# POWER_SUPPLY_2.net
KiCad netlist of a schematic drawn in Altium Designer
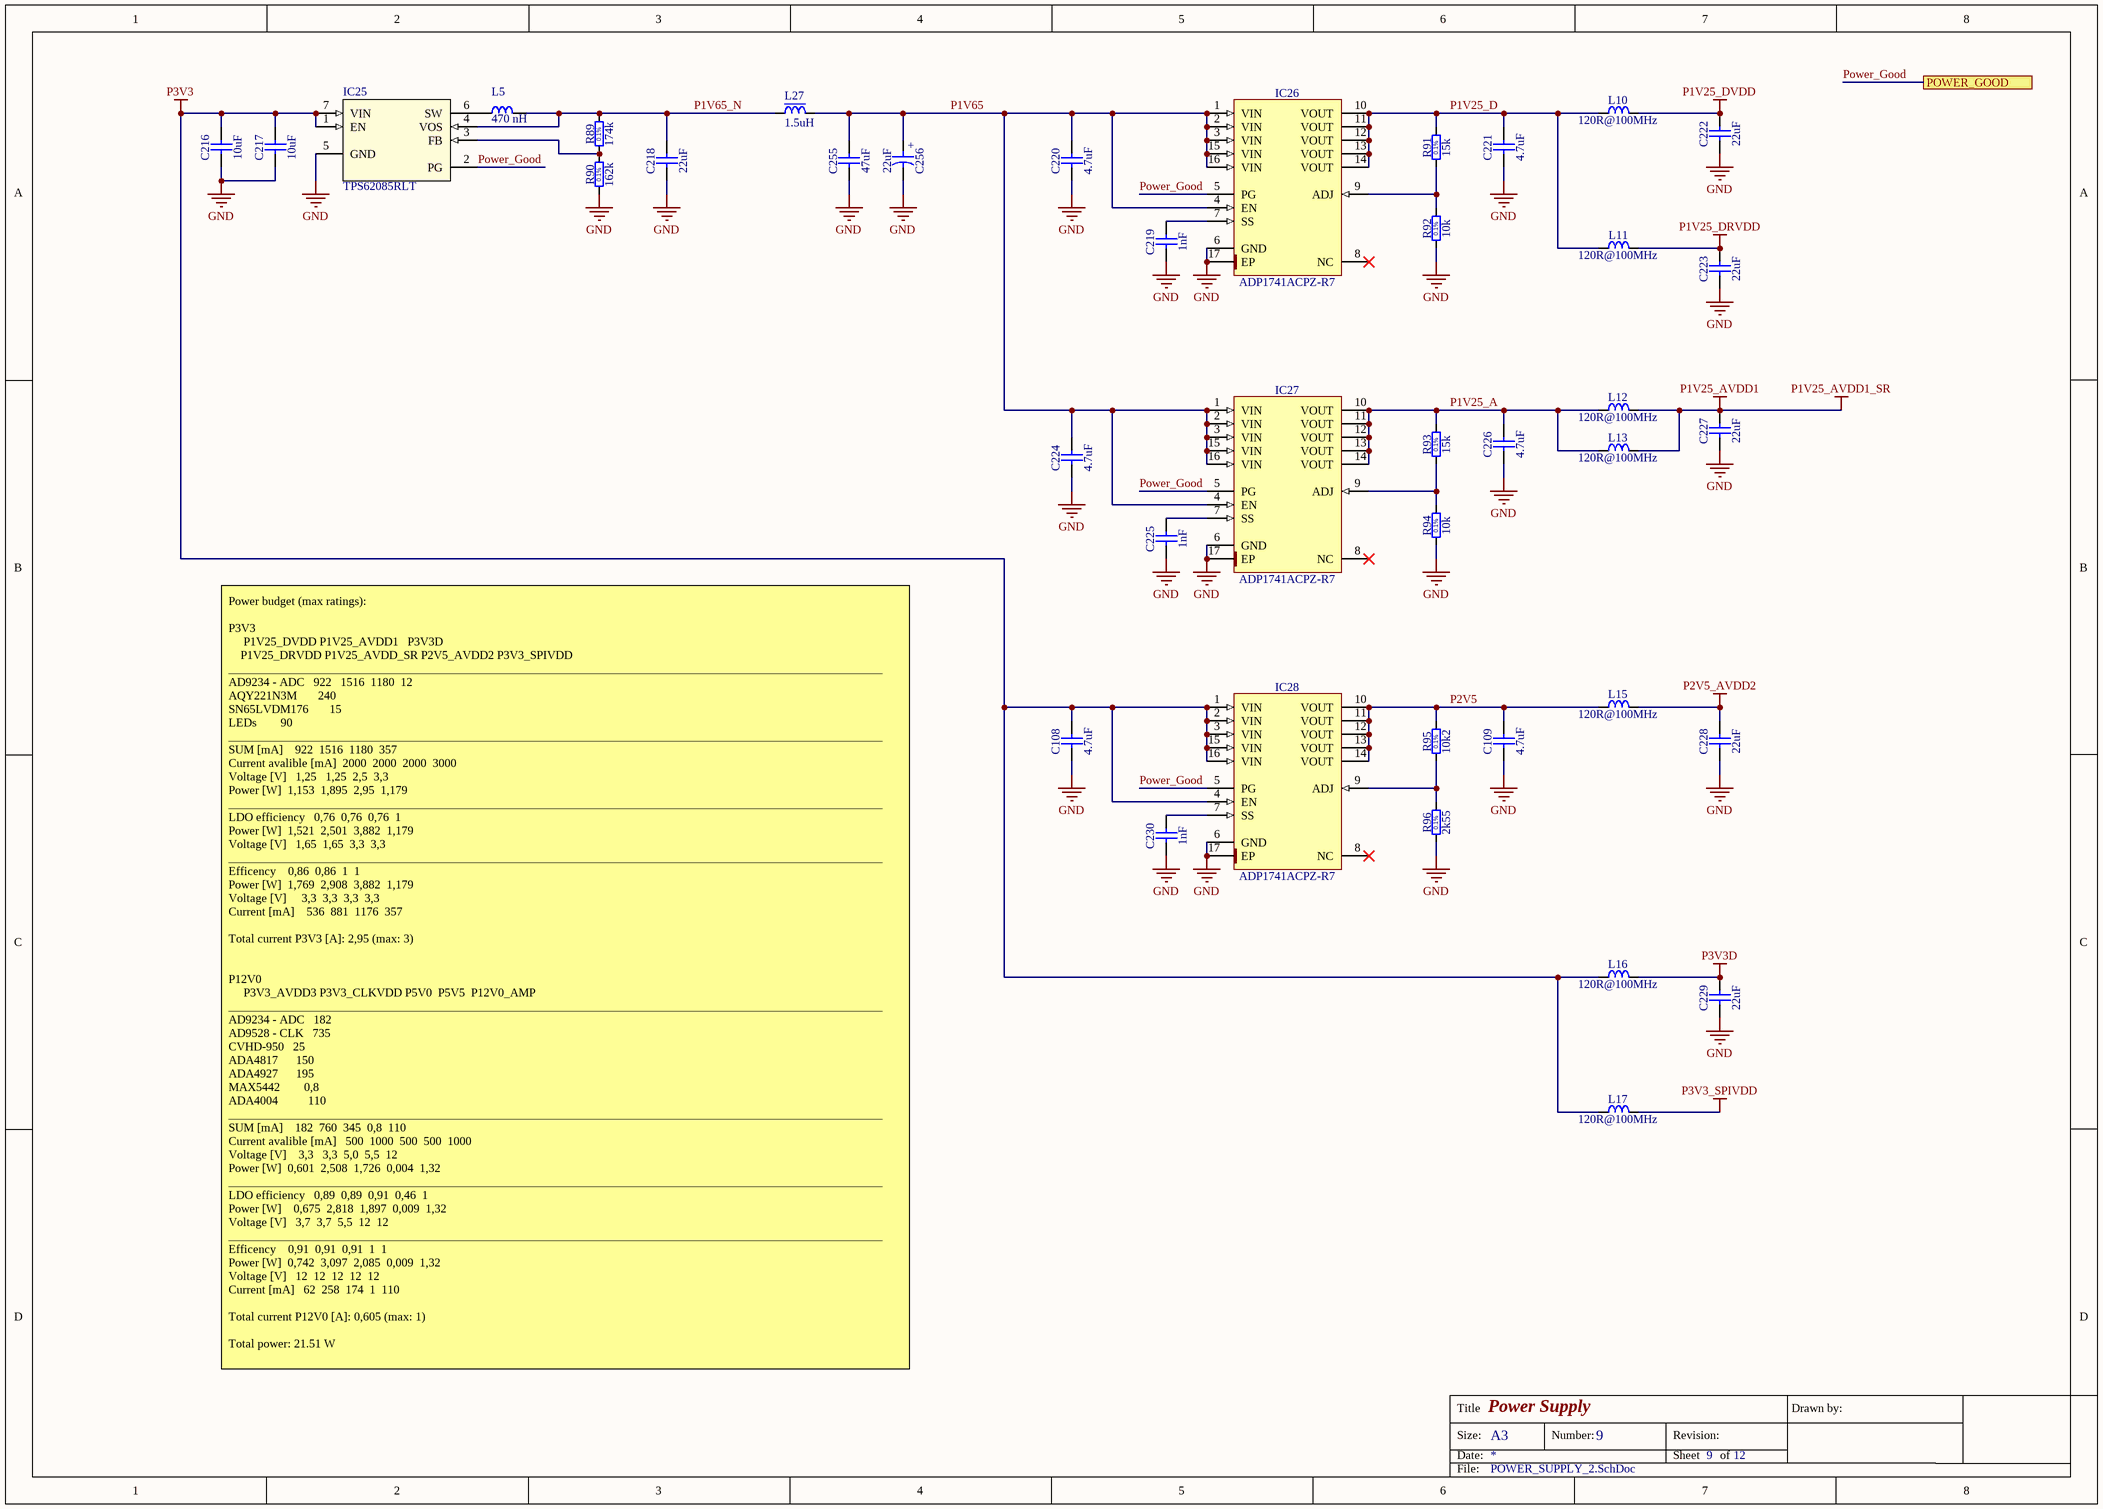
[diagram p0: POWER_SUPPLY_2.SchDoc]

(export (version "E")
  (design (tool "Eeschema 10.0.6"))
  (components
    (comp (ref "C108")
      (value "4.7uF")
      (footprint "CAPC1709X95N")
      (description "Non-polarised capacitor")
      (fields
        (field (name "PART NUMBER") "CC0603_4.7UF_16V_10%_X5R")
        (field (name "VOLTAGE") "16V")
        (field (name "AUTHOR") "CERN DEM JLC")
      )
      (libsource (lib "Capacitors") (part "Capacitor - non polarized"))
    )
    (comp (ref "C109")
      (value "4.7uF")
      (footprint "CAPC1709X95N")
      (description "Non-polarised capacitor")
      (fields
        (field (name "PART NUMBER") "CC0603_4.7UF_16V_10%_X5R")
        (field (name "VOLTAGE") "16V")
        (field (name "AUTHOR") "CERN DEM JLC")
      )
      (libsource (lib "Capacitors") (part "Capacitor - non polarized"))
    )
    (comp (ref "C216")
      (value "10uF")
      (footprint "CAPC1608X87N")
      (description "Non-polarised capacitor")
      (fields
        (field (name "PART NUMBER") "CC0603_10UF_6.3V_20%_X5R")
        (field (name "VOLTAGE") "6.3V")
        (field (name "AUTHOR") "CERN DEM JLC")
      )
      (libsource (lib "Capacitors") (part "Capacitor - non polarized"))
    )
    (comp (ref "C217")
      (value "10uF")
      (footprint "CAPC1608X87N")
      (description "Non-polarised capacitor")
      (fields
        (field (name "PART NUMBER") "CC0603_10UF_6.3V_20%_X5R")
        (field (name "VOLTAGE") "6.3V")
        (field (name "AUTHOR") "CERN DEM JLC")
      )
      (libsource (lib "Capacitors") (part "Capacitor - non polarized"))
    )
    (comp (ref "C218")
      (value "22uF")
      (footprint "CAPC2012X95N")
      (description "Non-polarised capacitor, Low ESR")
      (fields
        (field (name "PART NUMBER") "CC0805_22UF_6.3V_20%_X5R")
        (field (name "VOLTAGE") "6.3V")
        (field (name "AUTHOR") "*")
      )
      (libsource (lib "FMC_ADC") (part "JMK212ABJ226MD"))
    )
    (comp (ref "C219")
      (value "1nF")
      (footprint "CAPC0603X33N")
      (description "Non-polarised capacitor")
      (fields
        (field (name "PART NUMBER") "CC0201_1NF_16V_10%_X5R")
        (field (name "VOLTAGE") "16V")
        (field (name "AUTHOR") "CERN DEM JLC")
      )
      (libsource (lib "Capacitors") (part "Capacitor - non polarized"))
    )
    (comp (ref "C220")
      (value "4.7uF")
      (footprint "CAPC1709X95N")
      (description "Non-polarised capacitor")
      (fields
        (field (name "PART NUMBER") "CC0603_4.7UF_16V_10%_X5R")
        (field (name "VOLTAGE") "16V")
        (field (name "AUTHOR") "CERN DEM JLC")
      )
      (libsource (lib "Capacitors") (part "Capacitor - non polarized"))
    )
    (comp (ref "C221")
      (value "4.7uF")
      (footprint "CAPC1709X95N")
      (description "Non-polarised capacitor")
      (fields
        (field (name "PART NUMBER") "CC0603_4.7UF_16V_10%_X5R")
        (field (name "VOLTAGE") "16V")
        (field (name "AUTHOR") "CERN DEM JLC")
      )
      (libsource (lib "Capacitors") (part "Capacitor - non polarized"))
    )
    (comp (ref "C222")
      (value "22uF")
      (footprint "CAPC1709X100N")
      (description "Non-polarised capacitor")
      (fields
        (field (name "PART NUMBER") "CC0603_22UF_6.3V_20%_X5R")
        (field (name "VOLTAGE") "6.3V")
        (field (name "AUTHOR") "CERN DEM JLC")
      )
      (libsource (lib "Capacitors") (part "Capacitor - non polarized"))
    )
    (comp (ref "C223")
      (value "22uF")
      (footprint "CAPC1709X100N")
      (description "Non-polarised capacitor")
      (fields
        (field (name "PART NUMBER") "CC0603_22UF_6.3V_20%_X5R")
        (field (name "VOLTAGE") "6.3V")
        (field (name "AUTHOR") "CERN DEM JLC")
      )
      (libsource (lib "Capacitors") (part "Capacitor - non polarized"))
    )
    (comp (ref "C224")
      (value "4.7uF")
      (footprint "CAPC1709X95N")
      (description "Non-polarised capacitor")
      (fields
        (field (name "PART NUMBER") "CC0603_4.7UF_16V_10%_X5R")
        (field (name "VOLTAGE") "16V")
        (field (name "AUTHOR") "CERN DEM JLC")
      )
      (libsource (lib "Capacitors") (part "Capacitor - non polarized"))
    )
    (comp (ref "C225")
      (value "1nF")
      (footprint "CAPC0603X33N")
      (description "Non-polarised capacitor")
      (fields
        (field (name "PART NUMBER") "CC0201_1NF_16V_10%_X5R")
        (field (name "VOLTAGE") "16V")
        (field (name "AUTHOR") "CERN DEM JLC")
      )
      (libsource (lib "Capacitors") (part "Capacitor - non polarized"))
    )
    (comp (ref "C226")
      (value "4.7uF")
      (footprint "CAPC1709X95N")
      (description "Non-polarised capacitor")
      (fields
        (field (name "PART NUMBER") "CC0603_4.7UF_16V_10%_X5R")
        (field (name "VOLTAGE") "16V")
        (field (name "AUTHOR") "CERN DEM JLC")
      )
      (libsource (lib "Capacitors") (part "Capacitor - non polarized"))
    )
    (comp (ref "C227")
      (value "22uF")
      (footprint "CAPC1709X100N")
      (description "Non-polarised capacitor")
      (fields
        (field (name "PART NUMBER") "CC0603_22UF_6.3V_20%_X5R")
        (field (name "VOLTAGE") "6.3V")
        (field (name "AUTHOR") "CERN DEM JLC")
      )
      (libsource (lib "Capacitors") (part "Capacitor - non polarized"))
    )
    (comp (ref "C228")
      (value "22uF")
      (footprint "CAPC1709X100N")
      (description "Non-polarised capacitor")
      (fields
        (field (name "PART NUMBER") "CC0603_22UF_6.3V_20%_X5R")
        (field (name "VOLTAGE") "6.3V")
        (field (name "AUTHOR") "CERN DEM JLC")
      )
      (libsource (lib "Capacitors") (part "Capacitor - non polarized"))
    )
    (comp (ref "C229")
      (value "22uF")
      (footprint "CAPC1709X100N")
      (description "Non-polarised capacitor")
      (fields
        (field (name "PART NUMBER") "CC0603_22UF_6.3V_20%_X5R")
        (field (name "VOLTAGE") "6.3V")
        (field (name "AUTHOR") "CERN DEM JLC")
      )
      (libsource (lib "Capacitors") (part "Capacitor - non polarized"))
    )
    (comp (ref "C230")
      (value "1nF")
      (footprint "CAPC0603X33N")
      (description "Non-polarised capacitor")
      (fields
        (field (name "PART NUMBER") "CC0201_1NF_16V_10%_X5R")
        (field (name "VOLTAGE") "16V")
        (field (name "AUTHOR") "CERN DEM JLC")
      )
      (libsource (lib "Capacitors") (part "Capacitor - non polarized"))
    )
    (comp (ref "C255")
      (value "47uF")
      (footprint "CAPC3225X270N")
      (description "Non-polarised capacitor")
      (fields
        (field (name "PART NUMBER") "CC1210_47UF_10V_20%_X5R")
        (field (name "VOLTAGE") "10V")
        (field (name "AUTHOR") "CERN DEM JLC")
      )
      (libsource (lib "Capacitors") (part "Capacitor - non polarized"))
    )
    (comp (ref "C256")
      (value "22uF")
      (footprint "CAPMP3528X210N")
      (description "Polarised capacitor")
      (fields
        (field (name "PART NUMBER") "CTE3528-21_22UF_10V_10%_LESR0700")
        (field (name "VOLTAGE") "10V")
        (field (name "AUTHOR") "CERN DEM JLC")
      )
      (libsource (lib "Capacitors") (part "Capacitor - polarized"))
    )
    (comp (ref "IC25")
      (value "TPS62085RLT")
      (footprint "RLT0007A")
      (description "3-A Step-Down Converter With Hiccup Short-Circuit Protection")
      (fields (field (name "MANUFACTURER") "Texas Instruments"))
      (libsource (lib "FMC_ADC") (part "TPS62085RLT"))
    )
    (comp (ref "IC26")
      (value "ADP1741ACPZ-R7")
      (footprint "QFN65P400X400X100-17N-S225")
      (description "2A, 0.75V to 3.0V Adjustable, Low-Dropout Linear Regulator")
      (fields (field (name "MANUFACTURER") "ANALOG DEVICES") (field (name "AUTHOR") "CERN DEM JLC"))
      (libsource (lib "ICs And Semiconductors") (part "ADP1741"))
    )
    (comp (ref "IC27")
      (value "ADP1741ACPZ-R7")
      (footprint "QFN65P400X400X100-17N-S225")
      (description "2A, 0.75V to 3.0V Adjustable, Low-Dropout Linear Regulator")
      (fields (field (name "MANUFACTURER") "ANALOG DEVICES") (field (name "AUTHOR") "CERN DEM JLC"))
      (libsource (lib "ICs And Semiconductors") (part "ADP1741"))
    )
    (comp (ref "IC28")
      (value "ADP1741ACPZ-R7")
      (footprint "QFN65P400X400X100-17N-S225")
      (description "2A, 0.75V to 3.0V Adjustable, Low-Dropout Linear Regulator")
      (fields (field (name "MANUFACTURER") "ANALOG DEVICES") (field (name "AUTHOR") "CERN DEM JLC"))
      (libsource (lib "ICs And Semiconductors") (part "ADP1741"))
    )
    (comp (ref "L5")
      (value "470 nH")
      (footprint "IND_IHLP-1212AE")
      (description "Inductor, Low DCR Series")
      (fields (field (name "TOLERANCE") "20%") (field (name "MANUFACTURER") "VISHAY"))
      (libsource (lib "FMC_ADC") (part "IHLP1212AEERR47M11"))
    )
    (comp (ref "L10")
      (value "120R@100MHz")
      (footprint "INDC1608X65N")
      (description "Inductor")
      (fields
        (field (name "PART NUMBER") "IND0603_MURATA_BLM18SG121TN1D")
        (field (name "POWER") "3A")
        (field (name "AUTHOR") "CERN DEM JLC")
      )
      (libsource (lib "Inductors & Transformers") (part "Inductor"))
    )
    (comp (ref "L11")
      (value "120R@100MHz")
      (footprint "INDC1608X65N")
      (description "Inductor")
      (fields
        (field (name "PART NUMBER") "IND0603_MURATA_BLM18SG121TN1D")
        (field (name "POWER") "3A")
        (field (name "AUTHOR") "CERN DEM JLC")
      )
      (libsource (lib "Inductors & Transformers") (part "Inductor"))
    )
    (comp (ref "L12")
      (value "120R@100MHz")
      (footprint "INDC1608X65N")
      (description "Inductor")
      (fields
        (field (name "PART NUMBER") "IND0603_MURATA_BLM18SG121TN1D")
        (field (name "POWER") "3A")
        (field (name "AUTHOR") "CERN DEM JLC")
      )
      (libsource (lib "Inductors & Transformers") (part "Inductor"))
    )
    (comp (ref "L13")
      (value "120R@100MHz")
      (footprint "INDC1608X65N")
      (description "Inductor")
      (fields
        (field (name "PART NUMBER") "IND0603_MURATA_BLM18SG121TN1D")
        (field (name "POWER") "3A")
        (field (name "AUTHOR") "CERN DEM JLC")
      )
      (libsource (lib "Inductors & Transformers") (part "Inductor"))
    )
    (comp (ref "L15")
      (value "120R@100MHz")
      (footprint "INDC1608X65N")
      (description "Inductor")
      (fields
        (field (name "PART NUMBER") "IND0603_MURATA_BLM18SG121TN1D")
        (field (name "POWER") "3A")
        (field (name "AUTHOR") "CERN DEM JLC")
      )
      (libsource (lib "Inductors & Transformers") (part "Inductor"))
    )
    (comp (ref "L16")
      (value "120R@100MHz")
      (footprint "INDC1608X65N")
      (description "Inductor")
      (fields
        (field (name "PART NUMBER") "IND0603_MURATA_BLM18SG121TN1D")
        (field (name "POWER") "3A")
        (field (name "AUTHOR") "CERN DEM JLC")
      )
      (libsource (lib "Inductors & Transformers") (part "Inductor"))
    )
    (comp (ref "L17")
      (value "120R@100MHz")
      (footprint "INDC1608X65N")
      (description "Inductor")
      (fields
        (field (name "PART NUMBER") "IND0603_MURATA_BLM18SG121TN1D")
        (field (name "POWER") "3A")
        (field (name "AUTHOR") "CERN DEM JLC")
      )
      (libsource (lib "Inductors & Transformers") (part "Inductor"))
    )
    (comp (ref "L27")
      (value "1.5uH")
      (footprint "IND_SPM4020")
      (description "Inductor With Core")
      (fields
        (field (name "PART NUMBER") "IND_1.5UH_20%_TDK_SPM4020-LR")
        (field (name "POWER") "6.3A")
        (field (name "AUTHOR") "CERN DEM MR")
      )
      (libsource (lib "FMC_ADC") (part "IND_1.5UH_20%_TDK_SPM4020-LR"))
    )
    (comp (ref "R89")
      (value "174k")
      (footprint "RESC2012X60N")
      (description "Resistor - 0.1%")
      (fields
        (field (name "PART NUMBER") "R0805_174K_0.1%_0.125W_25PPM")
        (field (name "POWER") "0.125W")
        (field (name "AUTHOR") "CERN DEM JLC")
      )
      (libsource (lib "Resistors") (part "Resistor - 0.1%"))
    )
    (comp (ref "R90")
      (value "162k")
      (footprint "RESC2012X60N")
      (description "Resistor - 0.1%")
      (fields
        (field (name "PART NUMBER") "R0805_162K_0.1%_0.125W_25PPM")
        (field (name "POWER") "0.125W")
        (field (name "AUTHOR") "CERN DEM JLC")
      )
      (libsource (lib "Resistors") (part "Resistor - 0.1%"))
    )
    (comp (ref "R91")
      (value "15k")
      (footprint "RESC1608X55N")
      (description "Resistor - 0.1%")
      (fields
        (field (name "PART NUMBER") "R0603_15K_0.1%_0.063W_10PPM")
        (field (name "POWER") "0.063W")
        (field (name "AUTHOR") "CERN DEM JLC")
      )
      (libsource (lib "Resistors") (part "Resistor - 0.1%"))
    )
    (comp (ref "R92")
      (value "10k")
      (footprint "RESC1608X55N")
      (description "Resistor - 0.1%")
      (fields
        (field (name "PART NUMBER") "R0603_10K_0.1%_0.063W_10PPM")
        (field (name "POWER") "0.063W")
        (field (name "AUTHOR") "CERN DEM JLC")
      )
      (libsource (lib "Resistors") (part "Resistor - 0.1%"))
    )
    (comp (ref "R93")
      (value "15k")
      (footprint "RESC1608X55N")
      (description "Resistor - 0.1%")
      (fields
        (field (name "PART NUMBER") "R0603_15K_0.1%_0.063W_10PPM")
        (field (name "POWER") "0.063W")
        (field (name "AUTHOR") "CERN DEM JLC")
      )
      (libsource (lib "Resistors") (part "Resistor - 0.1%"))
    )
    (comp (ref "R94")
      (value "10k")
      (footprint "RESC1608X55N")
      (description "Resistor - 0.1%")
      (fields
        (field (name "PART NUMBER") "R0603_10K_0.1%_0.063W_10PPM")
        (field (name "POWER") "0.063W")
        (field (name "AUTHOR") "CERN DEM JLC")
      )
      (libsource (lib "Resistors") (part "Resistor - 0.1%"))
    )
    (comp (ref "R95")
      (value "10k2")
      (footprint "RESC1608X55N")
      (description "Resistor - 0.1%")
      (fields
        (field (name "PART NUMBER") "R0603_10K2_0.1%_0.063W_10PPM")
        (field (name "POWER") "0.063W")
        (field (name "AUTHOR") "CERN DEM JLC")
      )
      (libsource (lib "Resistors") (part "Resistor - 0.1%"))
    )
    (comp (ref "R96")
      (value "2k55")
      (footprint "RESC1608X55N")
      (description "Resistor - 0.1%")
      (fields
        (field (name "PART NUMBER") "R0603_2K55_0.1%_0.063W_10PPM")
        (field (name "POWER") "0.063W")
        (field (name "AUTHOR") "CERN DEM JLC")
      )
      (libsource (lib "Resistors") (part "Resistor - 0.1%"))
    )
  )
  (nets
    (net (code "1") (name "/P1V25_A") (class "Default")
      (node (ref "C226") (pin "2") (pinfunction "2_2") (pintype "passive"))
      (node (ref "IC27") (pin "10") (pinfunction "VOUT_10") (pintype "power_in"))
      (node (ref "IC27") (pin "11") (pinfunction "VOUT_11") (pintype "power_in"))
      (node (ref "IC27") (pin "12") (pinfunction "VOUT_12") (pintype "power_in"))
      (node (ref "IC27") (pin "13") (pinfunction "VOUT_13") (pintype "power_in"))
      (node (ref "IC27") (pin "14") (pinfunction "VOUT_14") (pintype "power_in"))
      (node (ref "L12") (pin "1") (pinfunction "1_1") (pintype "passive"))
      (node (ref "L13") (pin "1") (pinfunction "1_1") (pintype "passive"))
      (node (ref "R93") (pin "2") (pinfunction "2_2") (pintype "passive"))
    )
    (net (code "2") (name "/P1V25_D") (class "Default")
      (node (ref "C221") (pin "2") (pinfunction "2_2") (pintype "passive"))
      (node (ref "IC26") (pin "10") (pinfunction "VOUT_10") (pintype "power_in"))
      (node (ref "IC26") (pin "11") (pinfunction "VOUT_11") (pintype "power_in"))
      (node (ref "IC26") (pin "12") (pinfunction "VOUT_12") (pintype "power_in"))
      (node (ref "IC26") (pin "13") (pinfunction "VOUT_13") (pintype "power_in"))
      (node (ref "IC26") (pin "14") (pinfunction "VOUT_14") (pintype "power_in"))
      (node (ref "L10") (pin "1") (pinfunction "1_1") (pintype "passive"))
      (node (ref "L11") (pin "1") (pinfunction "1_1") (pintype "passive"))
      (node (ref "R91") (pin "2") (pinfunction "2_2") (pintype "passive"))
    )
    (net (code "3") (name "/P1V65") (class "Default")
      (node (ref "C220") (pin "2") (pinfunction "2_2") (pintype "passive"))
      (node (ref "C224") (pin "2") (pinfunction "2_2") (pintype "passive"))
      (node (ref "C255") (pin "2") (pinfunction "2_2") (pintype "passive"))
      (node (ref "C256") (pin "1") (pinfunction "1_1") (pintype "passive"))
      (node (ref "IC26") (pin "1") (pinfunction "VIN_1") (pintype "input"))
      (node (ref "IC26") (pin "15") (pinfunction "VIN_15") (pintype "input"))
      (node (ref "IC26") (pin "16") (pinfunction "VIN_16") (pintype "input"))
      (node (ref "IC26") (pin "2") (pinfunction "VIN_2") (pintype "input"))
      (node (ref "IC26") (pin "3") (pinfunction "VIN_3") (pintype "input"))
      (node (ref "IC26") (pin "4") (pinfunction "EN_4") (pintype "input"))
      (node (ref "IC27") (pin "1") (pinfunction "VIN_1") (pintype "input"))
      (node (ref "IC27") (pin "15") (pinfunction "VIN_15") (pintype "input"))
      (node (ref "IC27") (pin "16") (pinfunction "VIN_16") (pintype "input"))
      (node (ref "IC27") (pin "2") (pinfunction "VIN_2") (pintype "input"))
      (node (ref "IC27") (pin "3") (pinfunction "VIN_3") (pintype "input"))
      (node (ref "IC27") (pin "4") (pinfunction "EN_4") (pintype "input"))
      (node (ref "L27") (pin "2") (pinfunction "2_2") (pintype "passive"))
    )
    (net (code "4") (name "/P1V65_N") (class "Default")
      (node (ref "C218") (pin "2") (pinfunction "2_2") (pintype "passive"))
      (node (ref "IC25") (pin "4") (pinfunction "VOS_4") (pintype "input"))
      (node (ref "L27") (pin "1") (pinfunction "1_1") (pintype "passive"))
      (node (ref "L5") (pin "1") (pinfunction "1_1") (pintype "passive"))
      (node (ref "R89") (pin "2") (pinfunction "2_2") (pintype "passive"))
    )
    (net (code "5") (name "/P2V5") (class "Default")
      (node (ref "C109") (pin "2") (pinfunction "2_2") (pintype "passive"))
      (node (ref "IC28") (pin "10") (pinfunction "VOUT_10") (pintype "power_in"))
      (node (ref "IC28") (pin "11") (pinfunction "VOUT_11") (pintype "power_in"))
      (node (ref "IC28") (pin "12") (pinfunction "VOUT_12") (pintype "power_in"))
      (node (ref "IC28") (pin "13") (pinfunction "VOUT_13") (pintype "power_in"))
      (node (ref "IC28") (pin "14") (pinfunction "VOUT_14") (pintype "power_in"))
      (node (ref "L15") (pin "1") (pinfunction "1_1") (pintype "passive"))
      (node (ref "R95") (pin "2") (pinfunction "2_2") (pintype "passive"))
    )
    (net (code "6") (name "/Power_Good") (class "Default")
      (node (ref "IC25") (pin "2") (pinfunction "PG_2") (pintype "open_collector"))
      (node (ref "IC26") (pin "5") (pinfunction "PG_5") (pintype "open_collector"))
      (node (ref "IC27") (pin "5") (pinfunction "PG_5") (pintype "open_collector"))
      (node (ref "IC28") (pin "5") (pinfunction "PG_5") (pintype "open_collector"))
    )
    (net (code "7") (name "GND") (class "Default")
      (node (ref "C108") (pin "1") (pinfunction "1_1") (pintype "passive"))
      (node (ref "C109") (pin "1") (pinfunction "1_1") (pintype "passive"))
      (node (ref "C216") (pin "1") (pinfunction "1_1") (pintype "passive"))
      (node (ref "C217") (pin "1") (pinfunction "1_1") (pintype "passive"))
      (node (ref "C218") (pin "1") (pinfunction "1_1") (pintype "passive"))
      (node (ref "C219") (pin "1") (pinfunction "1_1") (pintype "passive"))
      (node (ref "C220") (pin "1") (pinfunction "1_1") (pintype "passive"))
      (node (ref "C221") (pin "1") (pinfunction "1_1") (pintype "passive"))
      (node (ref "C222") (pin "1") (pinfunction "1_1") (pintype "passive"))
      (node (ref "C223") (pin "1") (pinfunction "1_1") (pintype "passive"))
      (node (ref "C224") (pin "1") (pinfunction "1_1") (pintype "passive"))
      (node (ref "C225") (pin "1") (pinfunction "1_1") (pintype "passive"))
      (node (ref "C226") (pin "1") (pinfunction "1_1") (pintype "passive"))
      (node (ref "C227") (pin "1") (pinfunction "1_1") (pintype "passive"))
      (node (ref "C228") (pin "1") (pinfunction "1_1") (pintype "passive"))
      (node (ref "C229") (pin "1") (pinfunction "1_1") (pintype "passive"))
      (node (ref "C230") (pin "1") (pinfunction "1_1") (pintype "passive"))
      (node (ref "C255") (pin "1") (pinfunction "1_1") (pintype "passive"))
      (node (ref "C256") (pin "2") (pinfunction "2_2") (pintype "passive"))
      (node (ref "IC25") (pin "5") (pinfunction "GND_5") (pintype "power_in"))
      (node (ref "IC26") (pin "17") (pinfunction "EP_17") (pintype "power_in"))
      (node (ref "IC26") (pin "6") (pinfunction "GND_6") (pintype "power_in"))
      (node (ref "IC27") (pin "17") (pinfunction "EP_17") (pintype "power_in"))
      (node (ref "IC27") (pin "6") (pinfunction "GND_6") (pintype "power_in"))
      (node (ref "IC28") (pin "17") (pinfunction "EP_17") (pintype "power_in"))
      (node (ref "IC28") (pin "6") (pinfunction "GND_6") (pintype "power_in"))
      (node (ref "R90") (pin "1") (pinfunction "1_1") (pintype "passive"))
      (node (ref "R92") (pin "1") (pinfunction "1_1") (pintype "passive"))
      (node (ref "R94") (pin "1") (pinfunction "1_1") (pintype "passive"))
      (node (ref "R96") (pin "1") (pinfunction "1_1") (pintype "passive"))
    )
    (net (code "8") (name "Net-(IC25-FB)") (class "Default")
      (node (ref "IC25") (pin "3") (pinfunction "FB_3") (pintype "input"))
      (node (ref "R89") (pin "1") (pinfunction "1_1") (pintype "passive"))
      (node (ref "R90") (pin "2") (pinfunction "2_2") (pintype "passive"))
    )
    (net (code "9") (name "Net-(IC25-SW)") (class "Default")
      (node (ref "IC25") (pin "6") (pinfunction "SW_6") (pintype "power_in"))
      (node (ref "L5") (pin "2") (pinfunction "2_2") (pintype "passive"))
    )
    (net (code "10") (name "Net-(IC26-ADJ)") (class "Default")
      (node (ref "IC26") (pin "9") (pinfunction "ADJ_9") (pintype "input"))
      (node (ref "R91") (pin "1") (pinfunction "1_1") (pintype "passive"))
      (node (ref "R92") (pin "2") (pinfunction "2_2") (pintype "passive"))
    )
    (net (code "11") (name "Net-(IC26-SS)") (class "Default")
      (node (ref "C219") (pin "2") (pinfunction "2_2") (pintype "passive"))
      (node (ref "IC26") (pin "7") (pinfunction "SS_7") (pintype "input"))
    )
    (net (code "12") (name "Net-(IC27-ADJ)") (class "Default")
      (node (ref "IC27") (pin "9") (pinfunction "ADJ_9") (pintype "input"))
      (node (ref "R93") (pin "1") (pinfunction "1_1") (pintype "passive"))
      (node (ref "R94") (pin "2") (pinfunction "2_2") (pintype "passive"))
    )
    (net (code "13") (name "Net-(IC27-SS)") (class "Default")
      (node (ref "C225") (pin "2") (pinfunction "2_2") (pintype "passive"))
      (node (ref "IC27") (pin "7") (pinfunction "SS_7") (pintype "input"))
    )
    (net (code "14") (name "Net-(IC28-ADJ)") (class "Default")
      (node (ref "IC28") (pin "9") (pinfunction "ADJ_9") (pintype "input"))
      (node (ref "R95") (pin "1") (pinfunction "1_1") (pintype "passive"))
      (node (ref "R96") (pin "2") (pinfunction "2_2") (pintype "passive"))
    )
    (net (code "15") (name "Net-(IC28-SS)") (class "Default")
      (node (ref "C230") (pin "2") (pinfunction "2_2") (pintype "passive"))
      (node (ref "IC28") (pin "7") (pinfunction "SS_7") (pintype "input"))
    )
    (net (code "16") (name "P1V25_AVDD1") (class "Default")
      (node (ref "C227") (pin "2") (pinfunction "2_2") (pintype "passive"))
      (node (ref "L12") (pin "2") (pinfunction "2_2") (pintype "passive"))
      (node (ref "L13") (pin "2") (pinfunction "2_2") (pintype "passive"))
    )
    (net (code "17") (name "P1V25_DRVDD") (class "Default")
      (node (ref "C223") (pin "2") (pinfunction "2_2") (pintype "passive"))
      (node (ref "L11") (pin "2") (pinfunction "2_2") (pintype "passive"))
    )
    (net (code "18") (name "P1V25_DVDD") (class "Default")
      (node (ref "C222") (pin "2") (pinfunction "2_2") (pintype "passive"))
      (node (ref "L10") (pin "2") (pinfunction "2_2") (pintype "passive"))
    )
    (net (code "19") (name "P2V5_AVDD2") (class "Default")
      (node (ref "C228") (pin "2") (pinfunction "2_2") (pintype "passive"))
      (node (ref "L15") (pin "2") (pinfunction "2_2") (pintype "passive"))
    )
    (net (code "20") (name "P3V3") (class "Default")
      (node (ref "C108") (pin "2") (pinfunction "2_2") (pintype "passive"))
      (node (ref "C216") (pin "2") (pinfunction "2_2") (pintype "passive"))
      (node (ref "C217") (pin "2") (pinfunction "2_2") (pintype "passive"))
      (node (ref "IC25") (pin "1") (pinfunction "EN_1") (pintype "input"))
      (node (ref "IC25") (pin "7") (pinfunction "VIN_7") (pintype "input"))
      (node (ref "IC28") (pin "1") (pinfunction "VIN_1") (pintype "input"))
      (node (ref "IC28") (pin "15") (pinfunction "VIN_15") (pintype "input"))
      (node (ref "IC28") (pin "16") (pinfunction "VIN_16") (pintype "input"))
      (node (ref "IC28") (pin "2") (pinfunction "VIN_2") (pintype "input"))
      (node (ref "IC28") (pin "3") (pinfunction "VIN_3") (pintype "input"))
      (node (ref "IC28") (pin "4") (pinfunction "EN_4") (pintype "input"))
      (node (ref "L16") (pin "1") (pinfunction "1_1") (pintype "passive"))
      (node (ref "L17") (pin "1") (pinfunction "1_1") (pintype "passive"))
    )
    (net (code "21") (name "P3V3D") (class "Default")
      (node (ref "C229") (pin "2") (pinfunction "2_2") (pintype "passive"))
      (node (ref "L16") (pin "2") (pinfunction "2_2") (pintype "passive"))
    )
    (net (code "22") (name "P3V3_SPIVDD") (class "Default")
      (node (ref "L17") (pin "2") (pinfunction "2_2") (pintype "passive"))
    )
    (net (code "23") (name "unconnected-(IC26-NC-Pad8)") (class "Default")
      (node (ref "IC26") (pin "8") (pinfunction "NC_8") (pintype "passive+no_connect"))
    )
    (net (code "24") (name "unconnected-(IC27-NC-Pad8)") (class "Default")
      (node (ref "IC27") (pin "8") (pinfunction "NC_8") (pintype "passive+no_connect"))
    )
    (net (code "25") (name "unconnected-(IC28-NC-Pad8)") (class "Default")
      (node (ref "IC28") (pin "8") (pinfunction "NC_8") (pintype "passive+no_connect"))
    )
  )
)
